# PIR_Shield.net
KiCad netlist of a schematic drawn in EAGLE
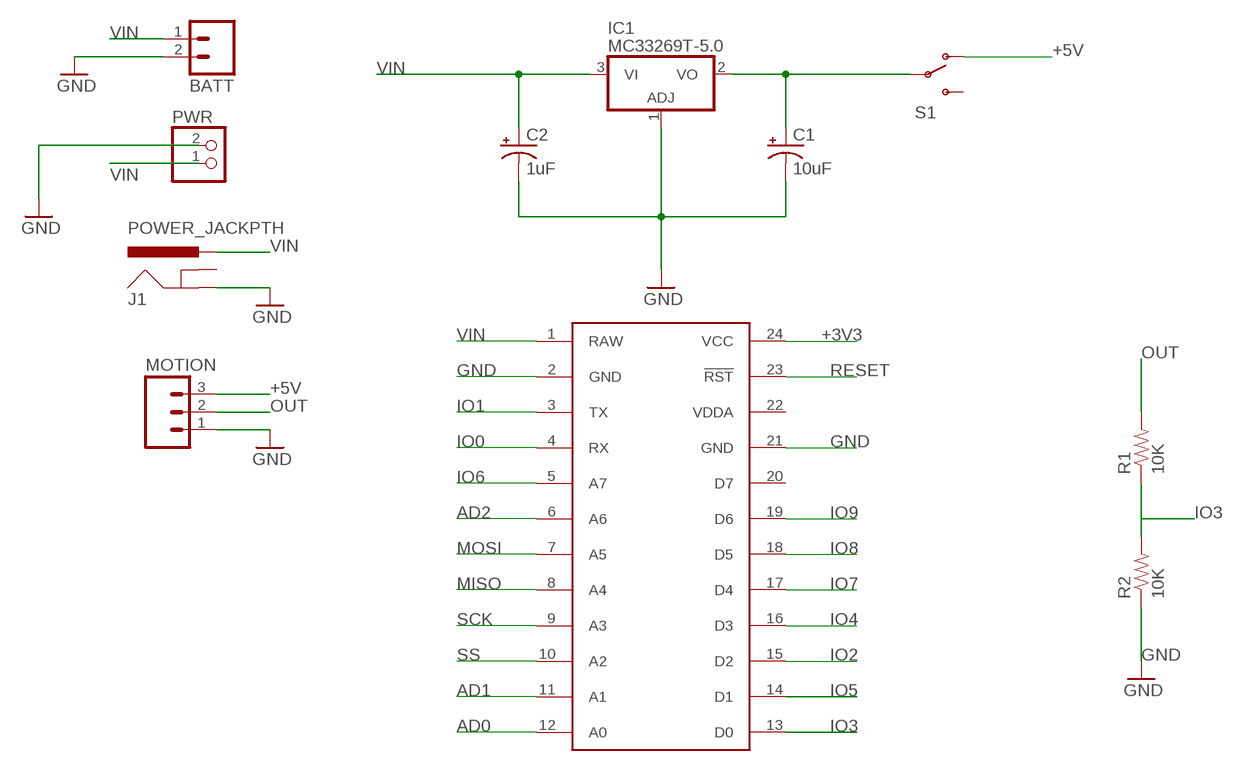
[diagram p0: schematic, sheet 1]

(export (version "E")
  (design (tool "Eeschema 10.0.6"))
  (components
    (comp (ref "BATT")
      (value "M02LOCK")
      (footprint "eagle-import:1X02_LOCK")
      (libsource (lib "eagle-import") (part "M02LOCK"))
    )
    (comp (ref "C1")
      (value "10uF")
      (footprint "eagle-import:CPOL-RADIAL-10UF-25V")
      (libsource (lib "eagle-import") (part "CAP_POLPTH2"))
    )
    (comp (ref "C2")
      (value "1uF")
      (footprint "eagle-import:CPOL-RADIAL-10UF-25V")
      (libsource (lib "eagle-import") (part "CAP_POLPTH2"))
    )
    (comp (ref "IC1")
      (value "MC33269T-5.0")
      (footprint "eagle-import:TO220V")
      (libsource (lib "eagle-import") (part "MC33269?T-5.0"))
    )
    (comp (ref "J1")
      (value "POWER_JACKPTH")
      (footprint "eagle-import:POWER_JACK_PTH")
      (libsource (lib "eagle-import") (part "POWER_JACKPTH"))
    )
    (comp (ref "MOTION")
      (value "M03PTH")
      (footprint "eagle-import:1X03")
      (libsource (lib "eagle-import") (part "M03PTH"))
    )
    (comp (ref "PWR")
      (value "JST_2PIN-THM")
      (footprint "eagle-import:JST-PH-2-THM")
      (libsource (lib "eagle-import") (part "JST_2PIN-THM"))
    )
    (comp (ref "R1")
      (value "10K")
      (footprint "eagle-import:AXIAL-0.3EZ")
      (libsource (lib "eagle-import") (part "RESISTOREZ"))
    )
    (comp (ref "R2")
      (value "10K")
      (footprint "eagle-import:AXIAL-0.3EZ")
      (libsource (lib "eagle-import") (part "RESISTOREZ"))
    )
    (comp (ref "S1")
      (value "SWITCH-SPDTPTH")
      (footprint "eagle-import:SWITCH-SPDT")
      (libsource (lib "eagle-import") (part "SWITCH-SPDTPTH"))
    )
    (comp (ref "U$1")
      (value "SPARK_CORECORE")
      (footprint "eagle-import:SPARK_CORE")
      (libsource (lib "eagle-import") (part "SPARK_CORECORE"))
    )
  )
  (nets
    (net (code "1") (name "/+3V3") (class "Default")
      (node (ref "U$1") (pin "24") (pinfunction "VCC_24") (pintype "power_in"))
    )
    (net (code "2") (name "/+5V") (class "Default")
      (node (ref "MOTION") (pin "3") (pinfunction "3_3") (pintype "passive"))
      (node (ref "S1") (pin "1") (pinfunction "O_1") (pintype "passive"))
    )
    (net (code "3") (name "/AD0") (class "Default")
      (node (ref "U$1") (pin "12") (pinfunction "A0_12") (pintype "bidirectional"))
    )
    (net (code "4") (name "/AD1") (class "Default")
      (node (ref "U$1") (pin "11") (pinfunction "A1_11") (pintype "bidirectional"))
    )
    (net (code "5") (name "/AD2") (class "Default")
      (node (ref "U$1") (pin "6") (pinfunction "A6_6") (pintype "bidirectional"))
    )
    (net (code "6") (name "/IO0") (class "Default")
      (node (ref "U$1") (pin "4") (pinfunction "RX_4") (pintype "bidirectional"))
    )
    (net (code "7") (name "/IO1") (class "Default")
      (node (ref "U$1") (pin "3") (pinfunction "TX_3") (pintype "bidirectional"))
    )
    (net (code "8") (name "/IO2") (class "Default")
      (node (ref "U$1") (pin "15") (pinfunction "D2_15") (pintype "bidirectional"))
    )
    (net (code "9") (name "/IO3") (class "Default")
      (node (ref "R1") (pin "P$1") (pinfunction "1_P$1") (pintype "passive"))
      (node (ref "R2") (pin "P$2") (pinfunction "2_P$2") (pintype "passive"))
      (node (ref "U$1") (pin "13") (pinfunction "D0_13") (pintype "bidirectional"))
    )
    (net (code "10") (name "/IO4") (class "Default")
      (node (ref "U$1") (pin "16") (pinfunction "D3_16") (pintype "bidirectional"))
    )
    (net (code "11") (name "/IO5") (class "Default")
      (node (ref "U$1") (pin "14") (pinfunction "D1_14") (pintype "bidirectional"))
    )
    (net (code "12") (name "/IO6") (class "Default")
      (node (ref "U$1") (pin "5") (pinfunction "A7_5") (pintype "bidirectional"))
    )
    (net (code "13") (name "/IO7") (class "Default")
      (node (ref "U$1") (pin "17") (pinfunction "D4_17") (pintype "bidirectional"))
    )
    (net (code "14") (name "/IO8") (class "Default")
      (node (ref "U$1") (pin "18") (pinfunction "D5_18") (pintype "bidirectional"))
    )
    (net (code "15") (name "/IO9") (class "Default")
      (node (ref "U$1") (pin "19") (pinfunction "D6_19") (pintype "bidirectional"))
    )
    (net (code "16") (name "/MISO") (class "Default")
      (node (ref "U$1") (pin "8") (pinfunction "A4_8") (pintype "bidirectional"))
    )
    (net (code "17") (name "/MOSI") (class "Default")
      (node (ref "U$1") (pin "7") (pinfunction "A5_7") (pintype "bidirectional"))
    )
    (net (code "18") (name "/OUT") (class "Default")
      (node (ref "MOTION") (pin "2") (pinfunction "2_2") (pintype "passive"))
      (node (ref "R1") (pin "P$2") (pinfunction "2_P$2") (pintype "passive"))
    )
    (net (code "19") (name "/RESET") (class "Default")
      (node (ref "U$1") (pin "23") (pinfunction "~{RST}_23") (pintype "bidirectional"))
    )
    (net (code "20") (name "/SCK") (class "Default")
      (node (ref "U$1") (pin "9") (pinfunction "A3_9") (pintype "bidirectional"))
    )
    (net (code "21") (name "/SS") (class "Default")
      (node (ref "U$1") (pin "10") (pinfunction "A2_10") (pintype "bidirectional"))
    )
    (net (code "22") (name "/VDDA") (class "Default")
      (node (ref "U$1") (pin "22") (pinfunction "VDDA_22") (pintype "power_in"))
    )
    (net (code "23") (name "/VIN") (class "Default")
      (node (ref "BATT") (pin "1") (pinfunction "1_1") (pintype "passive"))
      (node (ref "C2") (pin "1") (pinfunction "+_1") (pintype "passive"))
      (node (ref "IC1") (pin "3") (pinfunction "VI_3") (pintype "input"))
      (node (ref "J1") (pin "PWR") (pinfunction "PWR_PWR") (pintype "bidirectional"))
      (node (ref "PWR") (pin "1") (pinfunction "2_1") (pintype "passive"))
      (node (ref "U$1") (pin "1") (pinfunction "RAW_1") (pintype "power_in"))
    )
    (net (code "24") (name "GND") (class "Default")
      (node (ref "BATT") (pin "2") (pinfunction "2_2") (pintype "passive"))
      (node (ref "C1") (pin "2") (pinfunction "-_2") (pintype "passive"))
      (node (ref "C2") (pin "2") (pinfunction "-_2") (pintype "passive"))
      (node (ref "IC1") (pin "1") (pinfunction "ADJ_1") (pintype "input"))
      (node (ref "J1") (pin "GND") (pinfunction "GND_GND") (pintype "bidirectional"))
      (node (ref "MOTION") (pin "1") (pinfunction "1_1") (pintype "passive"))
      (node (ref "PWR") (pin "2") (pinfunction "1_2") (pintype "passive"))
      (node (ref "R2") (pin "P$1") (pinfunction "1_P$1") (pintype "passive"))
      (node (ref "U$1") (pin "2") (pinfunction "GND_2") (pintype "power_in"))
      (node (ref "U$1") (pin "21") (pinfunction "GND_21") (pintype "power_in"))
    )
    (net (code "25") (name "Net-(C1-+)") (class "Default")
      (node (ref "C1") (pin "1") (pinfunction "+_1") (pintype "passive"))
      (node (ref "IC1") (pin "2") (pinfunction "VO_2") (pintype "passive"))
      (node (ref "S1") (pin "2") (pinfunction "P_2") (pintype "passive"))
    )
    (net (code "26") (name "unconnected-(J1-PadGNDBREAK)") (class "Default")
      (node (ref "J1") (pin "GNDBREAK") (pinfunction "GNDBREAK_GNDBREAK") (pintype "bidirectional"))
    )
    (net (code "27") (name "unconnected-(S1-S-Pad3)") (class "Default")
      (node (ref "S1") (pin "3") (pinfunction "S_3") (pintype "passive"))
    )
    (net (code "28") (name "unconnected-(U$1-D7-Pad20)") (class "Default")
      (node (ref "U$1") (pin "20") (pinfunction "D7_20") (pintype "bidirectional"))
    )
  )
)
